# Dual_ESC_6-24V_3_7A_V1_Easy_EDA.net
KiCad netlist of a schematic drawn in EasyEDA Pro
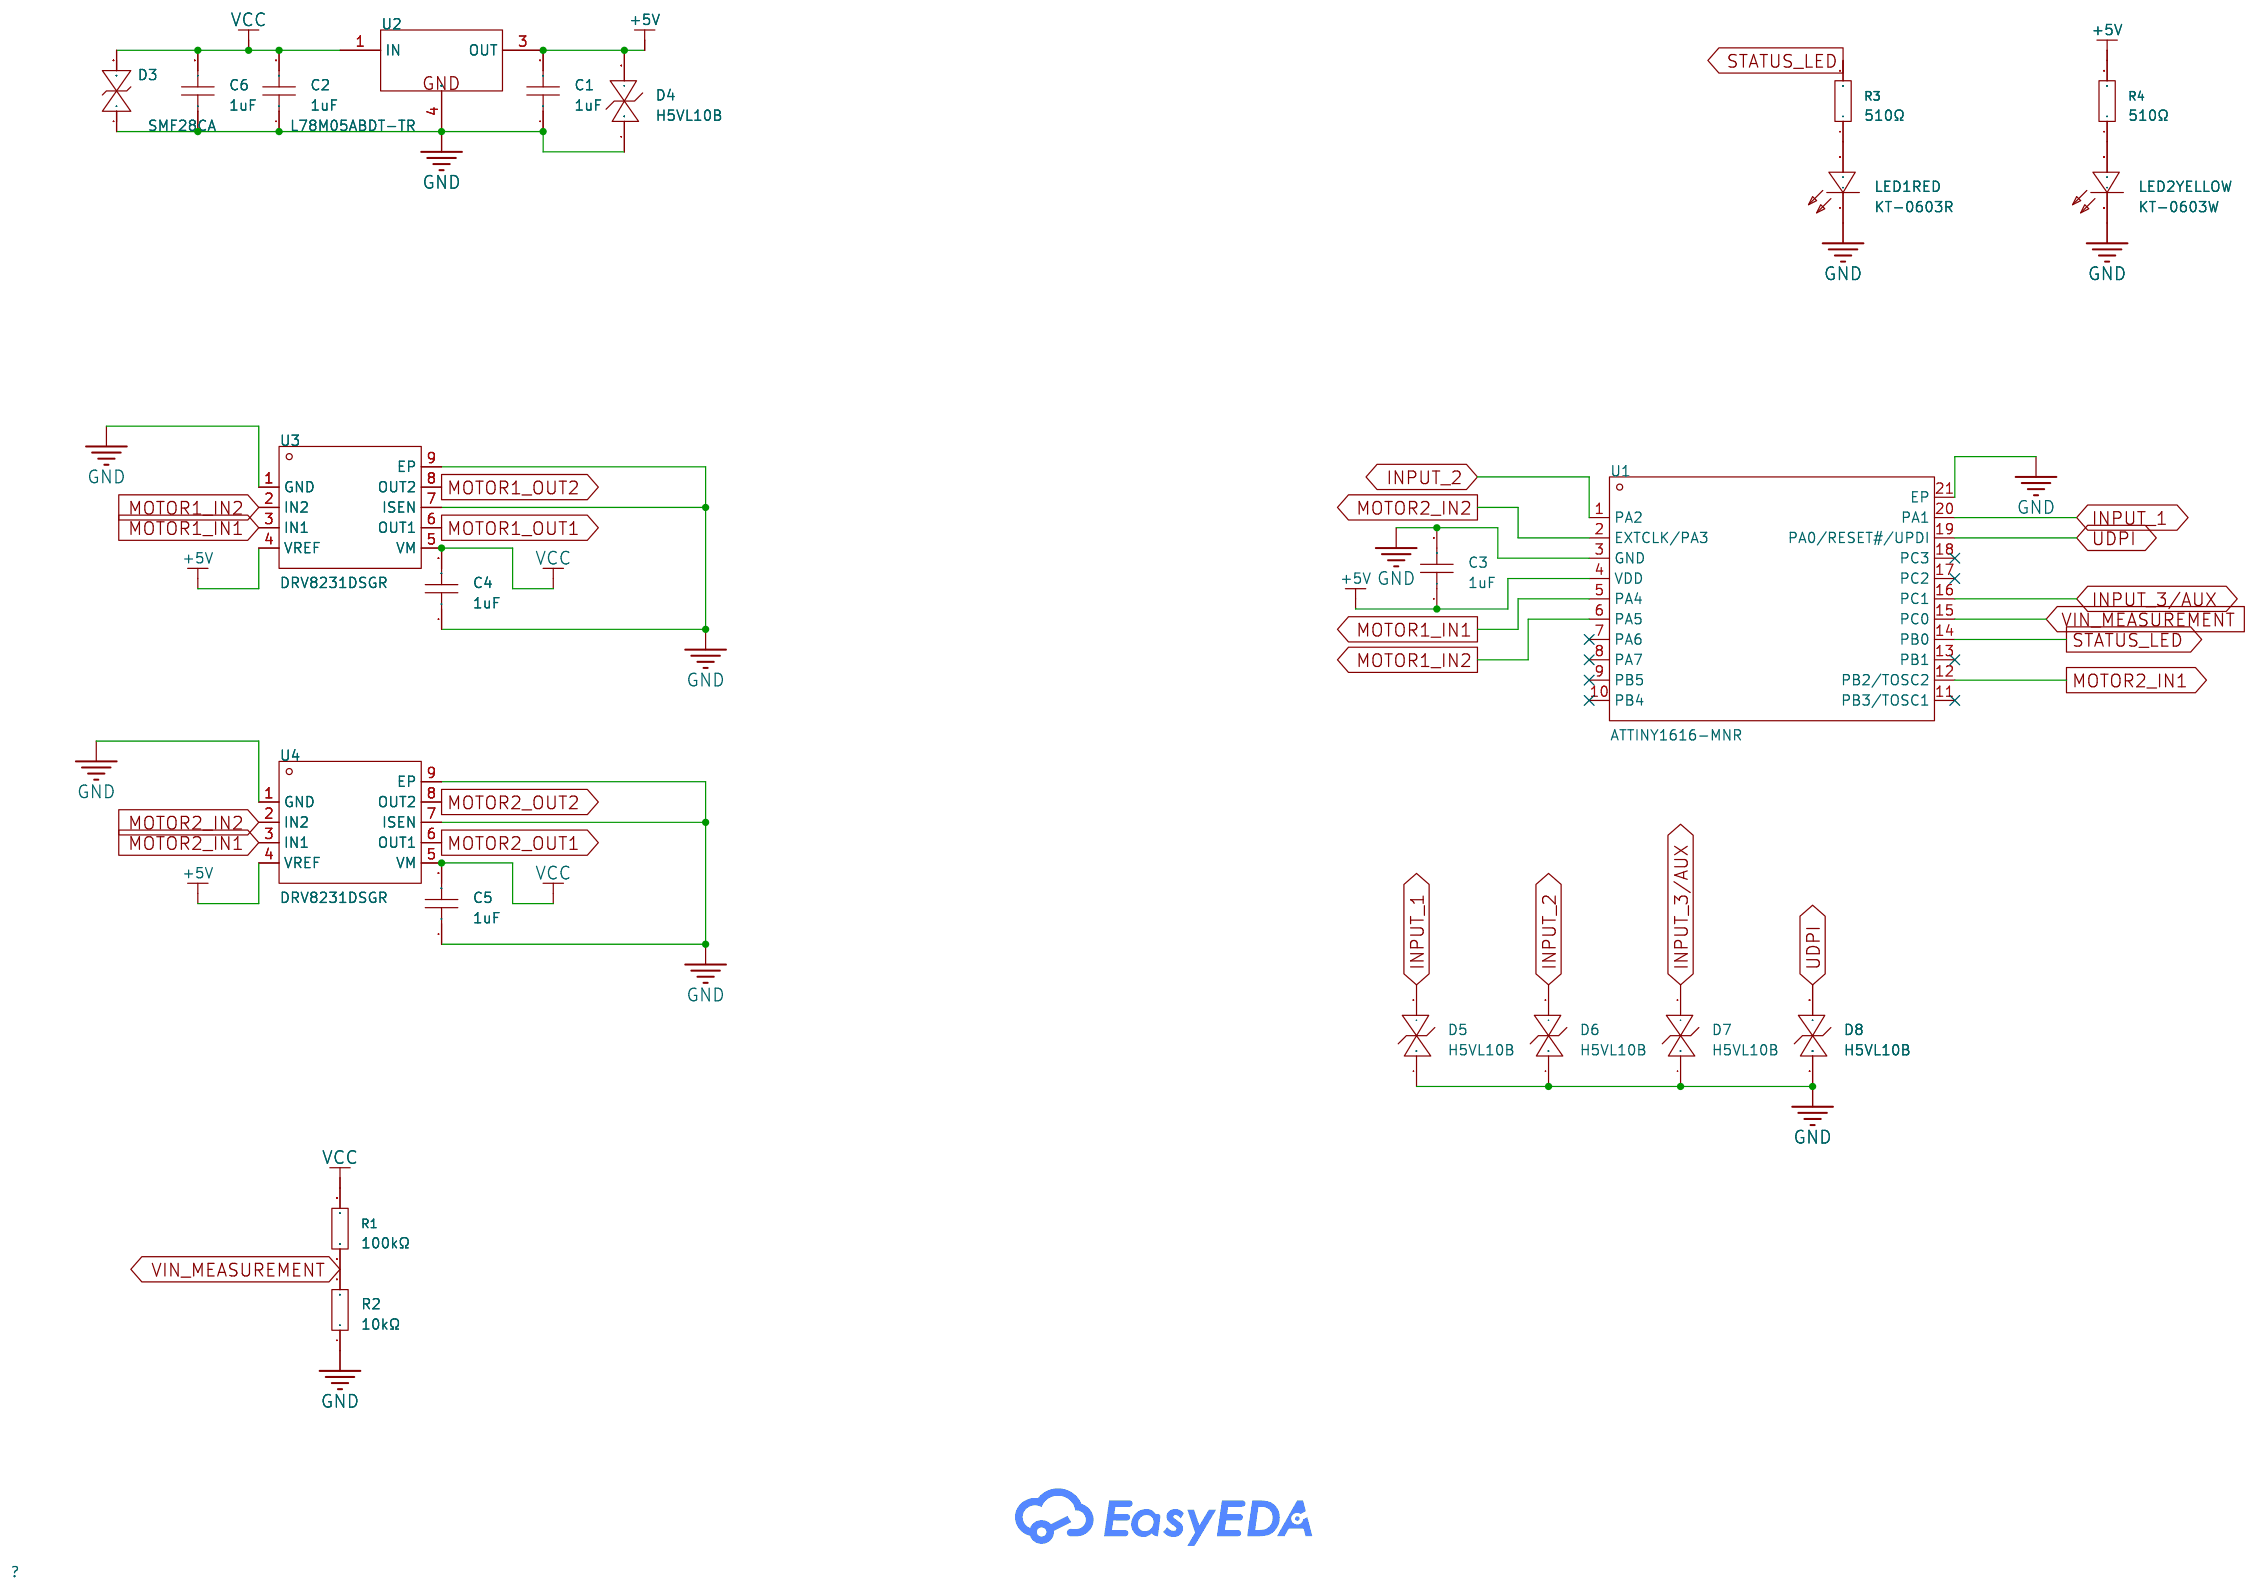
[diagram p0: schematic sheet]

(export (version "E")
  (design (tool "Eeschema 10.0.6"))
  (components
    (comp (ref "C1")
      (value "1uF")
      (footprint "easyedapro:C0402")
      (description "Capacitance:1uF Tolerance:±10% Tolerance:±10% Voltage Rating:25V Temperature Coefficient:X5R")
      (fields
        (field (name "Manufacturer Part") "CL05A105KA5NQNC")
        (field (name "Manufacturer") "SAMSUNG(三星)")
      )
      (libsource (lib "easyedapro") (part "CL05A105KA5NQNC"))
    )
    (comp (ref "C2")
      (value "1uF")
      (footprint "easyedapro:C0603")
      (description "Capacitance:1uF Tolerance:±10% Tolerance:±10% Voltage Rating:50V Temperature Coefficient:X5R")
      (fields
        (field (name "Manufacturer Part") "CL10A105KB8NNNC")
        (field (name "Manufacturer") "SAMSUNG(三星)")
      )
      (libsource (lib "easyedapro") (part "CL10A105KB8NNNC"))
    )
    (comp (ref "C3")
      (value "1uF")
      (footprint "easyedapro:C0402")
      (description "Capacitance:1uF Tolerance:±10% Tolerance:±10% Voltage Rating:25V Temperature Coefficient:X5R")
      (fields
        (field (name "Manufacturer Part") "CL05A105KA5NQNC")
        (field (name "Manufacturer") "SAMSUNG(三星)")
      )
      (libsource (lib "easyedapro") (part "CL05A105KA5NQNC"))
    )
    (comp (ref "C4")
      (value "1uF")
      (footprint "easyedapro:C0603")
      (description "Capacitance:1uF Tolerance:±10% Tolerance:±10% Voltage Rating:50V Temperature Coefficient:X5R")
      (fields
        (field (name "Manufacturer Part") "CL10A105KB8NNNC")
        (field (name "Manufacturer") "SAMSUNG(三星)")
      )
      (libsource (lib "easyedapro") (part "CL10A105KB8NNNC"))
    )
    (comp (ref "C5")
      (value "1uF")
      (footprint "easyedapro:C0603")
      (description "Capacitance:1uF Tolerance:±10% Tolerance:±10% Voltage Rating:50V Temperature Coefficient:X5R")
      (fields
        (field (name "Manufacturer Part") "CL10A105KB8NNNC")
        (field (name "Manufacturer") "SAMSUNG(三星)")
      )
      (libsource (lib "easyedapro") (part "CL10A105KB8NNNC"))
    )
    (comp (ref "C6")
      (value "1uF")
      (footprint "easyedapro:C0603")
      (description "Capacitance:1uF Tolerance:±10% Tolerance:±10% Voltage Rating:50V Temperature Coefficient:X5R")
      (fields
        (field (name "Manufacturer Part") "CL10A105KB8NNNC")
        (field (name "Manufacturer") "SAMSUNG(三星)")
      )
      (libsource (lib "easyedapro") (part "CL10A105KB8NNNC"))
    )
    (comp (ref "D3")
      (value "SMF28CA")
      (footprint "easyedapro:SOD-123FL_L2.7-W1.8-LS3.8-BI")
      (fields (field (name "Manufacturer") "R+O(宏嘉诚)"))
      (libsource (lib "easyedapro") (part "SMF28CA_C19077517"))
    )
    (comp (ref "D4")
      (value "H5VL10B")
      (footprint "easyedapro:SOD-882_L1.0-W0.6-BI")
      (fields (field (name "Manufacturer") "R+O(宏嘉诚)"))
      (libsource (lib "easyedapro") (part "H5VL10B"))
    )
    (comp (ref "D5")
      (value "H5VL10B")
      (footprint "easyedapro:SOD-882_L1.0-W0.6-BI")
      (fields (field (name "Manufacturer") "R+O(宏嘉诚)"))
      (libsource (lib "easyedapro") (part "H5VL10B"))
    )
    (comp (ref "D6")
      (value "H5VL10B")
      (footprint "easyedapro:SOD-882_L1.0-W0.6-BI")
      (fields (field (name "Manufacturer") "R+O(宏嘉诚)"))
      (libsource (lib "easyedapro") (part "H5VL10B"))
    )
    (comp (ref "D7")
      (value "H5VL10B")
      (footprint "easyedapro:SOD-882_L1.0-W0.6-BI")
      (fields (field (name "Manufacturer") "R+O(宏嘉诚)"))
      (libsource (lib "easyedapro") (part "H5VL10B"))
    )
    (comp (ref "D8")
      (value "H5VL10B")
      (footprint "easyedapro:SOD-882_L1.0-W0.6-BI")
      (fields (field (name "Manufacturer") "R+O(宏嘉诚)"))
      (libsource (lib "easyedapro") (part "H5VL10B"))
    )
    (comp (ref "LED1RED")
      (value "KT-0603R")
      (footprint "easyedapro:LED0603-RD")
      (fields (field (name "Manufacturer") "KENTO"))
      (libsource (lib "easyedapro") (part "KT-0603R"))
    )
    (comp (ref "LED2YELLOW")
      (value "KT-0603W")
      (footprint "easyedapro:LED0603-R-RD_WHITE")
      (fields (field (name "Manufacturer") "KENTO"))
      (libsource (lib "easyedapro") (part "0603White light_C2290"))
    )
    (comp (ref "R1")
      (value "100kΩ")
      (footprint "easyedapro:R0402")
      (fields
        (field (name "Manufacturer Part") "0402WGF1003TCE")
        (field (name "Manufacturer") "UNI-ROYAL(厚声)")
      )
      (libsource (lib "easyedapro") (part "0402WGF1003TCE"))
    )
    (comp (ref "R2")
      (value "10kΩ")
      (footprint "easyedapro:R0402")
      (fields
        (field (name "Manufacturer Part") "0402WGF1002TCE")
        (field (name "Manufacturer") "UNI-ROYAL(厚声)")
      )
      (libsource (lib "easyedapro") (part "0402WGF1002TCE"))
    )
    (comp (ref "R3")
      (value "510Ω")
      (footprint "easyedapro:R0402")
      (fields
        (field (name "Manufacturer Part") "0402WGF5100TCE")
        (field (name "Manufacturer") "UNI-ROYAL(厚声)")
      )
      (libsource (lib "easyedapro") (part "0402WGF5100TCE"))
    )
    (comp (ref "R4")
      (value "510Ω")
      (footprint "easyedapro:R0402")
      (fields
        (field (name "Manufacturer Part") "0402WGF5100TCE")
        (field (name "Manufacturer") "UNI-ROYAL(厚声)")
      )
      (libsource (lib "easyedapro") (part "0402WGF5100TCE"))
    )
    (comp (ref "U1")
      (value "ATTINY1616-MNR")
      (footprint "easyedapro:QFN-20_L3.0-W3.0-P0.40-BL-EP1.7")
      (fields (field (name "Manufacturer") "MICROCHIP(美国微芯)"))
      (libsource (lib "easyedapro") (part "ATTINY1616-MNR"))
    )
    (comp (ref "U2")
      (value "L78M05ABDT-TR")
      (footprint "easyedapro:TO-252-2_L6.5-W6.1-P4.58-LS10.0-TL")
      (fields (field (name "Manufacturer") "ST(意法半导体)"))
      (libsource (lib "easyedapro") (part "L78M05ABDT-TR"))
    )
    (comp (ref "U3")
      (value "DRV8231DSGR")
      (footprint "easyedapro:WSON-8_L2.0-W2.0-P0.50-TL-EP")
      (fields (field (name "Manufacturer") "TI(德州仪器)"))
      (libsource (lib "easyedapro") (part "DRV8231DSGR"))
    )
    (comp (ref "U4")
      (value "DRV8231DSGR")
      (footprint "easyedapro:WSON-8_L2.0-W2.0-P0.50-TL-EP")
      (fields (field (name "Manufacturer") "TI(德州仪器)"))
      (libsource (lib "easyedapro") (part "DRV8231DSGR"))
    )
  )
  (nets
    (net (code "1") (name "+5V") (class "Default")
      (node (ref "C1") (pin "2") (pinfunction "2_2") (pintype "unspecified"))
      (node (ref "C3") (pin "1") (pinfunction "1_1") (pintype "unspecified"))
      (node (ref "D4") (pin "2") (pinfunction "A_2") (pintype "unspecified"))
      (node (ref "R4") (pin "2") (pinfunction "2_2") (pintype "input"))
      (node (ref "U1") (pin "4") (pinfunction "VDD_4") (pintype "unspecified"))
      (node (ref "U2") (pin "3") (pinfunction "OUT_3") (pintype "unspecified"))
      (node (ref "U3") (pin "4") (pinfunction "VREF_4") (pintype "unspecified"))
      (node (ref "U4") (pin "4") (pinfunction "VREF_4") (pintype "unspecified"))
    )
    (net (code "2") (name "GND") (class "Default")
      (node (ref "C1") (pin "1") (pinfunction "1_1") (pintype "unspecified"))
      (node (ref "C2") (pin "1") (pinfunction "1_1") (pintype "unspecified"))
      (node (ref "C3") (pin "2") (pinfunction "2_2") (pintype "unspecified"))
      (node (ref "C4") (pin "1") (pinfunction "1_1") (pintype "unspecified"))
      (node (ref "C5") (pin "1") (pinfunction "1_1") (pintype "unspecified"))
      (node (ref "C6") (pin "1") (pinfunction "1_1") (pintype "unspecified"))
      (node (ref "D3") (pin "1") (pinfunction "1_1") (pintype "unspecified"))
      (node (ref "D4") (pin "1") (pinfunction "C_1") (pintype "unspecified"))
      (node (ref "D5") (pin "1") (pinfunction "C_1") (pintype "unspecified"))
      (node (ref "D6") (pin "1") (pinfunction "C_1") (pintype "unspecified"))
      (node (ref "D7") (pin "1") (pinfunction "C_1") (pintype "unspecified"))
      (node (ref "D8") (pin "1") (pinfunction "C_1") (pintype "unspecified"))
      (node (ref "LED1RED") (pin "1") (pinfunction "K_1") (pintype "unspecified"))
      (node (ref "LED2YELLOW") (pin "2") (pinfunction "K_2") (pintype "unspecified"))
      (node (ref "R2") (pin "1") (pinfunction "1_1") (pintype "input"))
      (node (ref "U1") (pin "21") (pinfunction "EP_21") (pintype "unspecified"))
      (node (ref "U1") (pin "3") (pinfunction "GND_3") (pintype "unspecified"))
      (node (ref "U2") (pin "4") (pinfunction "GND_4") (pintype "unspecified"))
      (node (ref "U3") (pin "1") (pinfunction "GND_1") (pintype "unspecified"))
      (node (ref "U3") (pin "7") (pinfunction "ISEN_7") (pintype "unspecified"))
      (node (ref "U3") (pin "9") (pinfunction "EP_9") (pintype "unspecified"))
      (node (ref "U4") (pin "1") (pinfunction "GND_1") (pintype "unspecified"))
      (node (ref "U4") (pin "7") (pinfunction "ISEN_7") (pintype "unspecified"))
      (node (ref "U4") (pin "9") (pinfunction "EP_9") (pintype "unspecified"))
    )
    (net (code "3") (name "INPUT_1") (class "Default")
      (node (ref "D5") (pin "2") (pinfunction "A_2") (pintype "unspecified"))
      (node (ref "U1") (pin "20") (pinfunction "PA1_20") (pintype "unspecified"))
    )
    (net (code "4") (name "INPUT_2") (class "Default")
      (node (ref "D6") (pin "2") (pinfunction "A_2") (pintype "unspecified"))
      (node (ref "U1") (pin "1") (pinfunction "PA2_1") (pintype "unspecified"))
    )
    (net (code "5") (name "INPUT_3{slash}AUX") (class "Default")
      (node (ref "D7") (pin "2") (pinfunction "A_2") (pintype "unspecified"))
      (node (ref "U1") (pin "16") (pinfunction "PC1_16") (pintype "unspecified"))
    )
    (net (code "6") (name "MOTOR1_IN1") (class "Default")
      (node (ref "U1") (pin "5") (pinfunction "PA4_5") (pintype "unspecified"))
      (node (ref "U3") (pin "3") (pinfunction "IN1_3") (pintype "unspecified"))
    )
    (net (code "7") (name "MOTOR1_IN2") (class "Default")
      (node (ref "U1") (pin "6") (pinfunction "PA5_6") (pintype "unspecified"))
      (node (ref "U3") (pin "2") (pinfunction "IN2_2") (pintype "unspecified"))
    )
    (net (code "8") (name "MOTOR1_OUT1") (class "Default")
      (node (ref "U3") (pin "6") (pinfunction "OUT1_6") (pintype "unspecified"))
    )
    (net (code "9") (name "MOTOR1_OUT2") (class "Default")
      (node (ref "U3") (pin "8") (pinfunction "OUT2_8") (pintype "unspecified"))
    )
    (net (code "10") (name "MOTOR2_IN1") (class "Default")
      (node (ref "U1") (pin "12") (pinfunction "PB2/TOSC2_12") (pintype "unspecified"))
      (node (ref "U4") (pin "3") (pinfunction "IN1_3") (pintype "unspecified"))
    )
    (net (code "11") (name "MOTOR2_IN2") (class "Default")
      (node (ref "U1") (pin "2") (pinfunction "EXTCLK/PA3_2") (pintype "unspecified"))
      (node (ref "U4") (pin "2") (pinfunction "IN2_2") (pintype "unspecified"))
    )
    (net (code "12") (name "MOTOR2_OUT1") (class "Default")
      (node (ref "U4") (pin "6") (pinfunction "OUT1_6") (pintype "unspecified"))
    )
    (net (code "13") (name "MOTOR2_OUT2") (class "Default")
      (node (ref "U4") (pin "8") (pinfunction "OUT2_8") (pintype "unspecified"))
    )
    (net (code "14") (name "Net-(LED1RED-A)") (class "Default")
      (node (ref "LED1RED") (pin "2") (pinfunction "A_2") (pintype "unspecified"))
      (node (ref "R3") (pin "1") (pinfunction "1_1") (pintype "input"))
    )
    (net (code "15") (name "Net-(LED2YELLOW-A)") (class "Default")
      (node (ref "LED2YELLOW") (pin "1") (pinfunction "A_1") (pintype "unspecified"))
      (node (ref "R4") (pin "1") (pinfunction "1_1") (pintype "input"))
    )
    (net (code "16") (name "STATUS_LED") (class "Default")
      (node (ref "R3") (pin "2") (pinfunction "2_2") (pintype "input"))
      (node (ref "U1") (pin "14") (pinfunction "PB0_14") (pintype "unspecified"))
    )
    (net (code "17") (name "UDPI") (class "Default")
      (node (ref "D8") (pin "2") (pinfunction "A_2") (pintype "unspecified"))
      (node (ref "U1") (pin "19") (pinfunction "PA0/RESET#/UPDI_19") (pintype "unspecified"))
    )
    (net (code "18") (name "VCC") (class "Default")
      (node (ref "C2") (pin "2") (pinfunction "2_2") (pintype "unspecified"))
      (node (ref "C4") (pin "2") (pinfunction "2_2") (pintype "unspecified"))
      (node (ref "C5") (pin "2") (pinfunction "2_2") (pintype "unspecified"))
      (node (ref "C6") (pin "2") (pinfunction "2_2") (pintype "unspecified"))
      (node (ref "D3") (pin "2") (pinfunction "2_2") (pintype "unspecified"))
      (node (ref "R1") (pin "2") (pinfunction "2_2") (pintype "input"))
      (node (ref "U2") (pin "1") (pinfunction "IN_1") (pintype "unspecified"))
      (node (ref "U3") (pin "5") (pinfunction "VM_5") (pintype "unspecified"))
      (node (ref "U4") (pin "5") (pinfunction "VM_5") (pintype "unspecified"))
    )
    (net (code "19") (name "VIN_MEASUREMENT") (class "Default")
      (node (ref "R1") (pin "1") (pinfunction "1_1") (pintype "input"))
      (node (ref "R2") (pin "2") (pinfunction "2_2") (pintype "input"))
      (node (ref "U1") (pin "15") (pinfunction "PC0_15") (pintype "unspecified"))
    )
    (net (code "20") (name "unconnected-(U1-PA6-Pad7)") (class "Default")
      (node (ref "U1") (pin "7") (pinfunction "PA6_7") (pintype "unspecified+no_connect"))
    )
    (net (code "21") (name "unconnected-(U1-PA7-Pad8)") (class "Default")
      (node (ref "U1") (pin "8") (pinfunction "PA7_8") (pintype "unspecified+no_connect"))
    )
    (net (code "22") (name "unconnected-(U1-PB1-Pad13)") (class "Default")
      (node (ref "U1") (pin "13") (pinfunction "PB1_13") (pintype "unspecified+no_connect"))
    )
    (net (code "23") (name "unconnected-(U1-PB3{slash}TOSC1-Pad11)") (class "Default")
      (node (ref "U1") (pin "11") (pinfunction "PB3/TOSC1_11") (pintype "unspecified+no_connect"))
    )
    (net (code "24") (name "unconnected-(U1-PB4-Pad10)") (class "Default")
      (node (ref "U1") (pin "10") (pinfunction "PB4_10") (pintype "unspecified+no_connect"))
    )
    (net (code "25") (name "unconnected-(U1-PB5-Pad9)") (class "Default")
      (node (ref "U1") (pin "9") (pinfunction "PB5_9") (pintype "unspecified+no_connect"))
    )
    (net (code "26") (name "unconnected-(U1-PC2-Pad17)") (class "Default")
      (node (ref "U1") (pin "17") (pinfunction "PC2_17") (pintype "unspecified+no_connect"))
    )
    (net (code "27") (name "unconnected-(U1-PC3-Pad18)") (class "Default")
      (node (ref "U1") (pin "18") (pinfunction "PC3_18") (pintype "unspecified+no_connect"))
    )
  )
)
